# MCU.net
KiCad netlist of a schematic drawn in Altium Designer
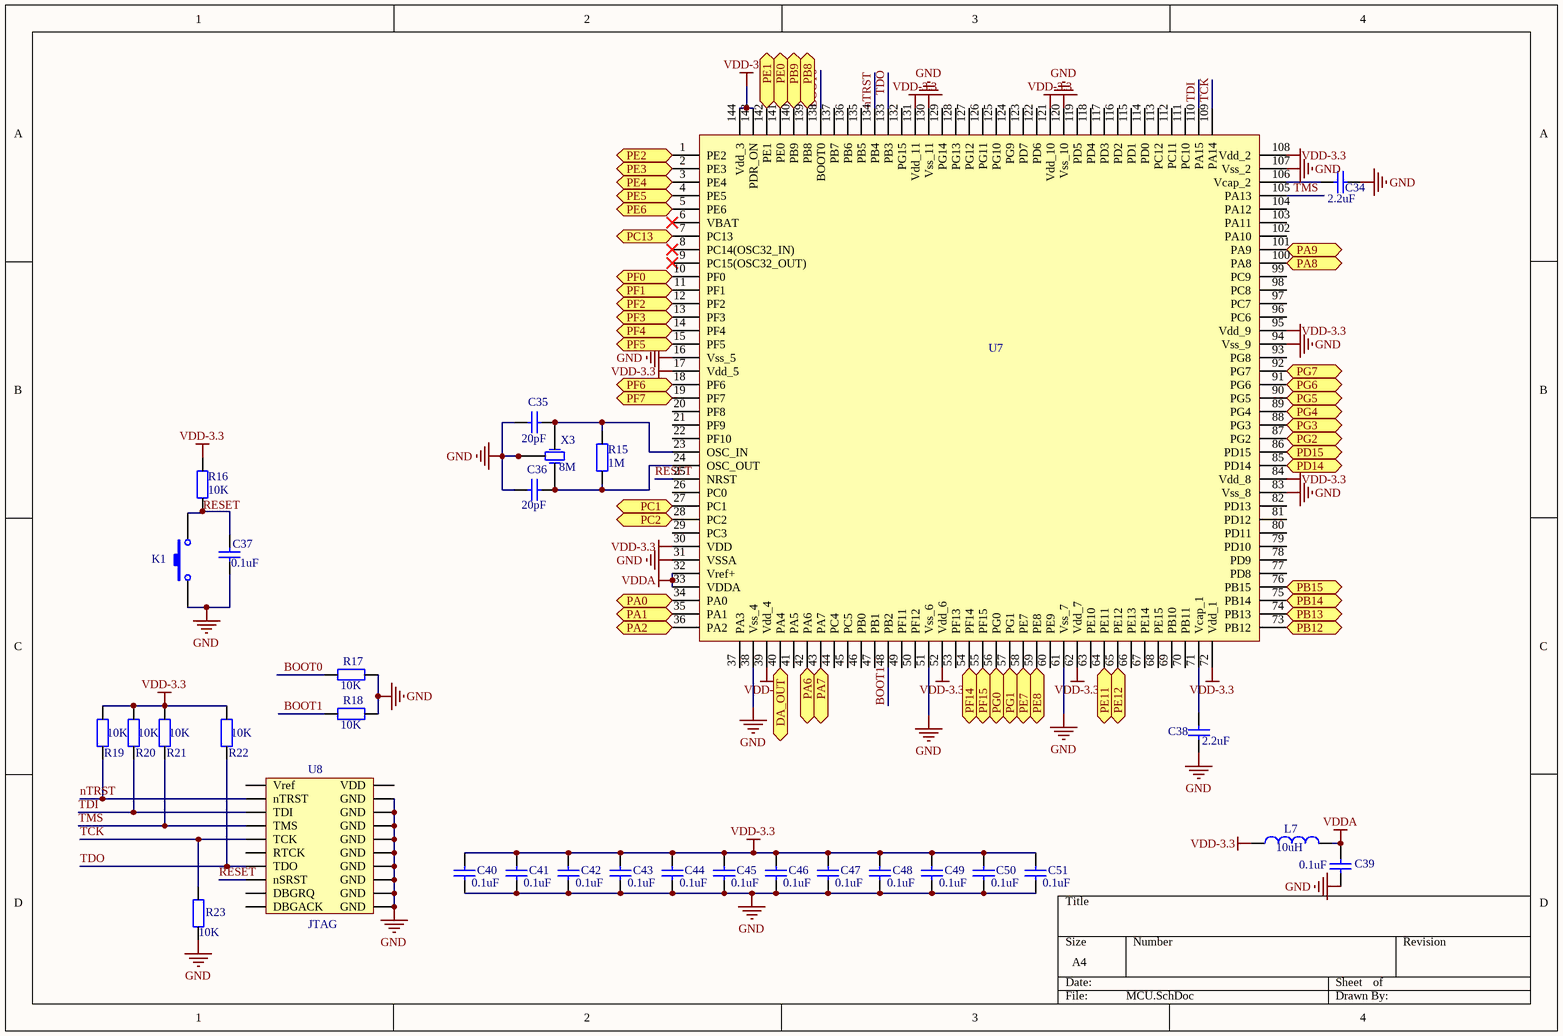
[diagram p0: MCU.SchDoc]

(export (version "E")
  (design (tool "Eeschema 10.0.6"))
  (components
    (comp (ref "C34")
      (value "2.2uF")
      (footprint "0603")
      (fields (field (name "Comment") "Capacitor-0603"))
      (libsource (lib "原理图库") (part "Capacitor-0603"))
    )
    (comp (ref "C35")
      (value "20pF")
      (footprint "0603")
      (fields (field (name "Comment") "Capacitor-0603"))
      (libsource (lib "原理图库") (part "Capacitor-0603"))
    )
    (comp (ref "C36")
      (value "20pF")
      (footprint "0603")
      (fields (field (name "Comment") "Capacitor-0603"))
      (libsource (lib "原理图库") (part "Capacitor-0603"))
    )
    (comp (ref "C37")
      (value "0.1uF")
      (footprint "0603")
      (fields (field (name "Comment") "Capacitor-0805"))
      (libsource (lib "原理图库") (part "Capacitor-0805"))
    )
    (comp (ref "C38")
      (value "2.2uF")
      (footprint "0603")
      (fields (field (name "Comment") "Capacitor-0603"))
      (libsource (lib "原理图库") (part "Capacitor-0603"))
    )
    (comp (ref "C39")
      (value "0.1uF")
      (footprint "0603")
      (fields (field (name "Comment") "Capacitor-0805"))
      (libsource (lib "集成库—大岐") (part "Capacitor-0805"))
    )
    (comp (ref "C40")
      (value "0.1uF")
      (footprint "0603")
      (fields (field (name "Comment") "Capacitor-0603"))
      (libsource (lib "原理图库") (part "Capacitor-0603"))
    )
    (comp (ref "C41")
      (value "0.1uF")
      (footprint "0603")
      (fields (field (name "Comment") "Capacitor-0603"))
      (libsource (lib "原理图库") (part "Capacitor-0603"))
    )
    (comp (ref "C42")
      (value "0.1uF")
      (footprint "0603")
      (fields (field (name "Comment") "Capacitor-0603"))
      (libsource (lib "原理图库") (part "Capacitor-0603"))
    )
    (comp (ref "C43")
      (value "0.1uF")
      (footprint "0603")
      (fields (field (name "Comment") "Capacitor-0603"))
      (libsource (lib "原理图库") (part "Capacitor-0603"))
    )
    (comp (ref "C44")
      (value "0.1uF")
      (footprint "0603")
      (fields (field (name "Comment") "Capacitor-0603"))
      (libsource (lib "原理图库") (part "Capacitor-0603"))
    )
    (comp (ref "C45")
      (value "0.1uF")
      (footprint "0603")
      (fields (field (name "Comment") "Capacitor-0603"))
      (libsource (lib "原理图库") (part "Capacitor-0603"))
    )
    (comp (ref "C46")
      (value "0.1uF")
      (footprint "0603")
      (fields (field (name "Comment") "Capacitor-0603"))
      (libsource (lib "原理图库") (part "Capacitor-0603"))
    )
    (comp (ref "C47")
      (value "0.1uF")
      (footprint "0603")
      (fields (field (name "Comment") "Capacitor-0603"))
      (libsource (lib "原理图库") (part "Capacitor-0603"))
    )
    (comp (ref "C48")
      (value "0.1uF")
      (footprint "0603")
      (fields (field (name "Comment") "Capacitor-0603"))
      (libsource (lib "原理图库") (part "Capacitor-0603"))
    )
    (comp (ref "C49")
      (value "0.1uF")
      (footprint "0603")
      (fields (field (name "Comment") "Capacitor-0603"))
      (libsource (lib "原理图库") (part "Capacitor-0603"))
    )
    (comp (ref "C50")
      (value "0.1uF")
      (footprint "0603")
      (fields (field (name "Comment") "Capacitor-0603"))
      (libsource (lib "原理图库") (part "Capacitor-0603"))
    )
    (comp (ref "C51")
      (value "0.1uF")
      (footprint "0603")
      (fields (field (name "Comment") "Capacitor-0603"))
      (libsource (lib "原理图库") (part "Capacitor-0603"))
    )
    (comp (ref "K1") (value "按键") (footprint "贴片按键") (libsource (lib "原理图库") (part "按键")))
    (comp (ref "L7")
      (value "10uH")
      (footprint "0805")
      (fields (field (name "Comment") "Inductor"))
      (libsource (lib "集成库—大岐") (part "Inductor"))
    )
    (comp (ref "R15")
      (value "1M")
      (footprint "0603")
      (fields (field (name "Comment") "Resistor-0603"))
      (libsource (lib "原理图库") (part "Resistor-0603"))
    )
    (comp (ref "R16")
      (value "10K")
      (footprint "0603")
      (fields (field (name "Comment") "Resistor-0805"))
      (libsource (lib "原理图库") (part "Resistor-0805"))
    )
    (comp (ref "R17")
      (value "10K")
      (footprint "0603")
      (fields (field (name "Comment") "Resistor-0805"))
      (libsource (lib "") (part "Resistor-0805_1"))
    )
    (comp (ref "R18")
      (value "10K")
      (footprint "0603")
      (fields (field (name "Comment") "Resistor-0805"))
      (libsource (lib "") (part "Resistor-0805_1"))
    )
    (comp (ref "R19")
      (value "10K")
      (footprint "0603")
      (fields (field (name "Comment") "Resistor-0805"))
      (libsource (lib "原理图库") (part "Resistor-0805"))
    )
    (comp (ref "R20")
      (value "10K")
      (footprint "0603")
      (fields (field (name "Comment") "Resistor-0805"))
      (libsource (lib "原理图库") (part "Resistor-0805"))
    )
    (comp (ref "R21")
      (value "10K")
      (footprint "0603")
      (fields (field (name "Comment") "Resistor-0805"))
      (libsource (lib "原理图库") (part "Resistor-0805"))
    )
    (comp (ref "R22")
      (value "10K")
      (footprint "0603")
      (fields (field (name "Comment") "Resistor-0805"))
      (libsource (lib "原理图库") (part "Resistor-0805"))
    )
    (comp (ref "R23")
      (value "10K")
      (footprint "0603")
      (fields (field (name "Comment") "Resistor-0805"))
      (libsource (lib "原理图库") (part "Resistor-0805"))
    )
    (comp (ref "U7")
      (value "STM32F407ZET6")
      (footprint "Stm32f407ZET6 - duplicate")
      (fields (field (name "Comment") "STM32F407ZGT6"))
      (libsource (lib "原理图库") (part "STM32F407ZET6"))
    )
    (comp (ref "U8") (value "JTAG") (footprint "JTAG-20") (libsource (lib "原理图库") (part "JTAG")))
    (comp (ref "X3")
      (value "8M")
      (footprint "3225无源晶振")
      (fields (field (name "Comment") "3225无源晶振"))
      (libsource (lib "原理图库") (part "3225无源晶振"))
    )
  )
  (nets
    (net (code "1") (name "/BOOT0") (class "Default")
      (node (ref "R17") (pin "2") (pinfunction "2_2") (pintype "passive"))
      (node (ref "U7") (pin "138") (pinfunction "BOOT0_138") (pintype "passive"))
    )
    (net (code "2") (name "/BOOT1") (class "Default")
      (node (ref "R18") (pin "2") (pinfunction "2_2") (pintype "passive"))
      (node (ref "U7") (pin "48") (pinfunction "PB2_48") (pintype "passive"))
    )
    (net (code "3") (name "/DA_OUT") (class "Default")
      (node (ref "U7") (pin "40") (pinfunction "PA4_40") (pintype "passive"))
    )
    (net (code "4") (name "/PA0") (class "Default")
      (node (ref "U7") (pin "34") (pinfunction "PA0_34") (pintype "passive"))
    )
    (net (code "5") (name "/PA1") (class "Default")
      (node (ref "U7") (pin "35") (pinfunction "PA1_35") (pintype "passive"))
    )
    (net (code "6") (name "/PA2") (class "Default")
      (node (ref "U7") (pin "36") (pinfunction "PA2_36") (pintype "passive"))
    )
    (net (code "7") (name "/PA6") (class "Default")
      (node (ref "U7") (pin "42") (pinfunction "PA6_42") (pintype "passive"))
    )
    (net (code "8") (name "/PA7") (class "Default")
      (node (ref "U7") (pin "43") (pinfunction "PA7_43") (pintype "passive"))
    )
    (net (code "9") (name "/PA8") (class "Default")
      (node (ref "U7") (pin "100") (pinfunction "PA8_100") (pintype "passive"))
    )
    (net (code "10") (name "/PA9") (class "Default")
      (node (ref "U7") (pin "101") (pinfunction "PA9_101") (pintype "passive"))
    )
    (net (code "11") (name "/PB8") (class "Default")
      (node (ref "U7") (pin "139") (pinfunction "PB8_139") (pintype "passive"))
    )
    (net (code "12") (name "/PB9") (class "Default")
      (node (ref "U7") (pin "140") (pinfunction "PB9_140") (pintype "passive"))
    )
    (net (code "13") (name "/PB12") (class "Default")
      (node (ref "U7") (pin "73") (pinfunction "PB12_73") (pintype "passive"))
    )
    (net (code "14") (name "/PB13") (class "Default")
      (node (ref "U7") (pin "74") (pinfunction "PB13_74") (pintype "passive"))
    )
    (net (code "15") (name "/PB14") (class "Default")
      (node (ref "U7") (pin "75") (pinfunction "PB14_75") (pintype "passive"))
    )
    (net (code "16") (name "/PB15") (class "Default")
      (node (ref "U7") (pin "76") (pinfunction "PB15_76") (pintype "passive"))
    )
    (net (code "17") (name "/PC1") (class "Default")
      (node (ref "U7") (pin "27") (pinfunction "PC1_27") (pintype "passive"))
    )
    (net (code "18") (name "/PC2") (class "Default")
      (node (ref "U7") (pin "28") (pinfunction "PC2_28") (pintype "passive"))
    )
    (net (code "19") (name "/PC13") (class "Default")
      (node (ref "U7") (pin "7") (pinfunction "PC13_7") (pintype "passive"))
    )
    (net (code "20") (name "/PD14") (class "Default")
      (node (ref "U7") (pin "85") (pinfunction "PD14_85") (pintype "passive"))
    )
    (net (code "21") (name "/PD15") (class "Default")
      (node (ref "U7") (pin "86") (pinfunction "PD15_86") (pintype "passive"))
    )
    (net (code "22") (name "/PE0") (class "Default")
      (node (ref "U7") (pin "141") (pinfunction "PE0_141") (pintype "passive"))
    )
    (net (code "23") (name "/PE1") (class "Default")
      (node (ref "U7") (pin "142") (pinfunction "PE1_142") (pintype "passive"))
    )
    (net (code "24") (name "/PE2") (class "Default")
      (node (ref "U7") (pin "1") (pinfunction "PE2_1") (pintype "passive"))
    )
    (net (code "25") (name "/PE3") (class "Default")
      (node (ref "U7") (pin "2") (pinfunction "PE3_2") (pintype "passive"))
    )
    (net (code "26") (name "/PE4") (class "Default")
      (node (ref "U7") (pin "3") (pinfunction "PE4_3") (pintype "passive"))
    )
    (net (code "27") (name "/PE5") (class "Default")
      (node (ref "U7") (pin "4") (pinfunction "PE5_4") (pintype "passive"))
    )
    (net (code "28") (name "/PE6") (class "Default")
      (node (ref "U7") (pin "5") (pinfunction "PE6_5") (pintype "passive"))
    )
    (net (code "29") (name "/PE7") (class "Default")
      (node (ref "U7") (pin "58") (pinfunction "PE7_58") (pintype "passive"))
    )
    (net (code "30") (name "/PE8") (class "Default")
      (node (ref "U7") (pin "59") (pinfunction "PE8_59") (pintype "passive"))
    )
    (net (code "31") (name "/PE11") (class "Default")
      (node (ref "U7") (pin "64") (pinfunction "PE11_64") (pintype "passive"))
    )
    (net (code "32") (name "/PE12") (class "Default")
      (node (ref "U7") (pin "65") (pinfunction "PE12_65") (pintype "passive"))
    )
    (net (code "33") (name "/PF0") (class "Default")
      (node (ref "U7") (pin "10") (pinfunction "PF0_10") (pintype "passive"))
    )
    (net (code "34") (name "/PF1") (class "Default")
      (node (ref "U7") (pin "11") (pinfunction "PF1_11") (pintype "passive"))
    )
    (net (code "35") (name "/PF2") (class "Default")
      (node (ref "U7") (pin "12") (pinfunction "PF2_12") (pintype "passive"))
    )
    (net (code "36") (name "/PF3") (class "Default")
      (node (ref "U7") (pin "13") (pinfunction "PF3_13") (pintype "passive"))
    )
    (net (code "37") (name "/PF4") (class "Default")
      (node (ref "U7") (pin "14") (pinfunction "PF4_14") (pintype "passive"))
    )
    (net (code "38") (name "/PF5") (class "Default")
      (node (ref "U7") (pin "15") (pinfunction "PF5_15") (pintype "passive"))
    )
    (net (code "39") (name "/PF6") (class "Default")
      (node (ref "U7") (pin "18") (pinfunction "PF6_18") (pintype "passive"))
    )
    (net (code "40") (name "/PF7") (class "Default")
      (node (ref "U7") (pin "19") (pinfunction "PF7_19") (pintype "passive"))
    )
    (net (code "41") (name "/PF14") (class "Default")
      (node (ref "U7") (pin "54") (pinfunction "PF14_54") (pintype "passive"))
    )
    (net (code "42") (name "/PF15") (class "Default")
      (node (ref "U7") (pin "55") (pinfunction "PF15_55") (pintype "passive"))
    )
    (net (code "43") (name "/PG0") (class "Default")
      (node (ref "U7") (pin "56") (pinfunction "PG0_56") (pintype "passive"))
    )
    (net (code "44") (name "/PG1") (class "Default")
      (node (ref "U7") (pin "57") (pinfunction "PG1_57") (pintype "passive"))
    )
    (net (code "45") (name "/PG2") (class "Default")
      (node (ref "U7") (pin "87") (pinfunction "PG2_87") (pintype "passive"))
    )
    (net (code "46") (name "/PG3") (class "Default")
      (node (ref "U7") (pin "88") (pinfunction "PG3_88") (pintype "passive"))
    )
    (net (code "47") (name "/PG4") (class "Default")
      (node (ref "U7") (pin "89") (pinfunction "PG4_89") (pintype "passive"))
    )
    (net (code "48") (name "/PG5") (class "Default")
      (node (ref "U7") (pin "90") (pinfunction "PG5_90") (pintype "passive"))
    )
    (net (code "49") (name "/PG6") (class "Default")
      (node (ref "U7") (pin "91") (pinfunction "PG6_91") (pintype "passive"))
    )
    (net (code "50") (name "/PG7") (class "Default")
      (node (ref "U7") (pin "92") (pinfunction "PG7_92") (pintype "passive"))
    )
    (net (code "51") (name "/RESET") (class "Default")
      (node (ref "C37") (pin "2") (pinfunction "2_2") (pintype "passive"))
      (node (ref "K1") (pin "2") (pinfunction "2_2") (pintype "passive"))
      (node (ref "R16") (pin "1") (pinfunction "1_1") (pintype "passive"))
      (node (ref "U7") (pin "25") (pinfunction "NRST_25") (pintype "passive"))
      (node (ref "U8") (pin "15") (pinfunction "nSRST_15") (pintype "passive"))
    )
    (net (code "52") (name "/TCK") (class "Default")
      (node (ref "R23") (pin "2") (pinfunction "2_2") (pintype "passive"))
      (node (ref "U7") (pin "109") (pinfunction "PA14_109") (pintype "passive"))
      (node (ref "U8") (pin "9") (pinfunction "TCK_9") (pintype "passive"))
    )
    (net (code "53") (name "/TDI") (class "Default")
      (node (ref "R20") (pin "1") (pinfunction "1_1") (pintype "passive"))
      (node (ref "U7") (pin "110") (pinfunction "PA15_110") (pintype "passive"))
      (node (ref "U8") (pin "5") (pinfunction "TDI_5") (pintype "passive"))
    )
    (net (code "54") (name "/TDO") (class "Default")
      (node (ref "R22") (pin "1") (pinfunction "1_1") (pintype "passive"))
      (node (ref "U7") (pin "133") (pinfunction "PB3_133") (pintype "passive"))
      (node (ref "U8") (pin "13") (pinfunction "TDO_13") (pintype "passive"))
    )
    (net (code "55") (name "/TMS") (class "Default")
      (node (ref "R21") (pin "1") (pinfunction "1_1") (pintype "passive"))
      (node (ref "U7") (pin "105") (pinfunction "PA13_105") (pintype "passive"))
      (node (ref "U8") (pin "7") (pinfunction "TMS_7") (pintype "passive"))
    )
    (net (code "56") (name "/nTRST") (class "Default")
      (node (ref "R19") (pin "1") (pinfunction "1_1") (pintype "passive"))
      (node (ref "U7") (pin "134") (pinfunction "PB4_134") (pintype "passive"))
      (node (ref "U8") (pin "3") (pinfunction "nTRST_3") (pintype "passive"))
    )
    (net (code "57") (name "GND") (class "Default")
      (node (ref "C34") (pin "2") (pinfunction "2_2") (pintype "passive"))
      (node (ref "C35") (pin "1") (pinfunction "1_1") (pintype "passive"))
      (node (ref "C36") (pin "1") (pinfunction "1_1") (pintype "passive"))
      (node (ref "C37") (pin "1") (pinfunction "1_1") (pintype "passive"))
      (node (ref "C38") (pin "1") (pinfunction "1_1") (pintype "passive"))
      (node (ref "C39") (pin "1") (pinfunction "1_1") (pintype "passive"))
      (node (ref "C40") (pin "1") (pinfunction "1_1") (pintype "passive"))
      (node (ref "C41") (pin "1") (pinfunction "1_1") (pintype "passive"))
      (node (ref "C42") (pin "1") (pinfunction "1_1") (pintype "passive"))
      (node (ref "C43") (pin "1") (pinfunction "1_1") (pintype "passive"))
      (node (ref "C44") (pin "1") (pinfunction "1_1") (pintype "passive"))
      (node (ref "C45") (pin "1") (pinfunction "1_1") (pintype "passive"))
      (node (ref "C46") (pin "1") (pinfunction "1_1") (pintype "passive"))
      (node (ref "C47") (pin "1") (pinfunction "1_1") (pintype "passive"))
      (node (ref "C48") (pin "1") (pinfunction "1_1") (pintype "passive"))
      (node (ref "C49") (pin "1") (pinfunction "1_1") (pintype "passive"))
      (node (ref "C50") (pin "1") (pinfunction "1_1") (pintype "passive"))
      (node (ref "C51") (pin "1") (pinfunction "1_1") (pintype "passive"))
      (node (ref "K1") (pin "1") (pinfunction "1_1") (pintype "passive"))
      (node (ref "R17") (pin "1") (pinfunction "1_1") (pintype "passive"))
      (node (ref "R18") (pin "1") (pinfunction "1_1") (pintype "passive"))
      (node (ref "R23") (pin "1") (pinfunction "1_1") (pintype "passive"))
      (node (ref "U7") (pin "107") (pinfunction "Vss_2_107") (pintype "passive"))
      (node (ref "U7") (pin "120") (pinfunction "Vss_10_120") (pintype "passive"))
      (node (ref "U7") (pin "130") (pinfunction "Vss_11_130") (pintype "passive"))
      (node (ref "U7") (pin "16") (pinfunction "Vss_5_16") (pintype "passive"))
      (node (ref "U7") (pin "31") (pinfunction "VSSA_31") (pintype "passive"))
      (node (ref "U7") (pin "38") (pinfunction "Vss_4_38") (pintype "passive"))
      (node (ref "U7") (pin "51") (pinfunction "Vss_6_51") (pintype "passive"))
      (node (ref "U7") (pin "61") (pinfunction "Vss_7_61") (pintype "passive"))
      (node (ref "U7") (pin "83") (pinfunction "Vss_8_83") (pintype "passive"))
      (node (ref "U7") (pin "94") (pinfunction "Vss_9_94") (pintype "passive"))
      (node (ref "U8") (pin "10") (pinfunction "GND_10") (pintype "passive"))
      (node (ref "U8") (pin "12") (pinfunction "GND_12") (pintype "passive"))
      (node (ref "U8") (pin "14") (pinfunction "GND_14") (pintype "passive"))
      (node (ref "U8") (pin "16") (pinfunction "GND_16") (pintype "passive"))
      (node (ref "U8") (pin "18") (pinfunction "GND_18") (pintype "passive"))
      (node (ref "U8") (pin "20") (pinfunction "GND_20") (pintype "passive"))
      (node (ref "U8") (pin "4") (pinfunction "GND_4") (pintype "passive"))
      (node (ref "U8") (pin "6") (pinfunction "GND_6") (pintype "passive"))
      (node (ref "U8") (pin "8") (pinfunction "GND_8") (pintype "passive"))
      (node (ref "X3") (pin "2") (pinfunction "GND_2") (pintype "passive"))
      (node (ref "X3") (pin "4") (pinfunction "GND_4") (pintype "passive"))
    )
    (net (code "58") (name "Net-(U7-OSC_IN)") (class "Default")
      (node (ref "C35") (pin "2") (pinfunction "2_2") (pintype "passive"))
      (node (ref "R15") (pin "2") (pinfunction "2_2") (pintype "passive"))
      (node (ref "U7") (pin "23") (pinfunction "OSC_IN_23") (pintype "passive"))
      (node (ref "X3") (pin "1") (pinfunction "OSC1_1") (pintype "passive"))
    )
    (net (code "59") (name "Net-(U7-OSC_OUT)") (class "Default")
      (node (ref "C36") (pin "2") (pinfunction "2_2") (pintype "passive"))
      (node (ref "R15") (pin "1") (pinfunction "1_1") (pintype "passive"))
      (node (ref "U7") (pin "24") (pinfunction "OSC_OUT_24") (pintype "passive"))
      (node (ref "X3") (pin "3") (pinfunction "OSC2_3") (pintype "passive"))
    )
    (net (code "60") (name "Net-(U7-Vcap_1)") (class "Default")
      (node (ref "C38") (pin "2") (pinfunction "2_2") (pintype "passive"))
      (node (ref "U7") (pin "71") (pinfunction "Vcap_1_71") (pintype "passive"))
    )
    (net (code "61") (name "Net-(U7-Vcap_2)") (class "Default")
      (node (ref "C34") (pin "1") (pinfunction "1_1") (pintype "passive"))
      (node (ref "U7") (pin "106") (pinfunction "Vcap_2_106") (pintype "passive"))
    )
    (net (code "62") (name "VDD-3.3") (class "Default")
      (node (ref "C40") (pin "2") (pinfunction "2_2") (pintype "passive"))
      (node (ref "C41") (pin "2") (pinfunction "2_2") (pintype "passive"))
      (node (ref "C42") (pin "2") (pinfunction "2_2") (pintype "passive"))
      (node (ref "C43") (pin "2") (pinfunction "2_2") (pintype "passive"))
      (node (ref "C44") (pin "2") (pinfunction "2_2") (pintype "passive"))
      (node (ref "C45") (pin "2") (pinfunction "2_2") (pintype "passive"))
      (node (ref "C46") (pin "2") (pinfunction "2_2") (pintype "passive"))
      (node (ref "C47") (pin "2") (pinfunction "2_2") (pintype "passive"))
      (node (ref "C48") (pin "2") (pinfunction "2_2") (pintype "passive"))
      (node (ref "C49") (pin "2") (pinfunction "2_2") (pintype "passive"))
      (node (ref "C50") (pin "2") (pinfunction "2_2") (pintype "passive"))
      (node (ref "C51") (pin "2") (pinfunction "2_2") (pintype "passive"))
      (node (ref "L7") (pin "1") (pinfunction "1_1") (pintype "passive"))
      (node (ref "R16") (pin "2") (pinfunction "2_2") (pintype "passive"))
      (node (ref "R19") (pin "2") (pinfunction "2_2") (pintype "passive"))
      (node (ref "R20") (pin "2") (pinfunction "2_2") (pintype "passive"))
      (node (ref "R21") (pin "2") (pinfunction "2_2") (pintype "passive"))
      (node (ref "R22") (pin "2") (pinfunction "2_2") (pintype "passive"))
      (node (ref "U7") (pin "108") (pinfunction "Vdd_2_108") (pintype "passive"))
      (node (ref "U7") (pin "121") (pinfunction "Vdd_10_121") (pintype "passive"))
      (node (ref "U7") (pin "131") (pinfunction "Vdd_11_131") (pintype "passive"))
      (node (ref "U7") (pin "143") (pinfunction "PDR_ON_143") (pintype "passive"))
      (node (ref "U7") (pin "144") (pinfunction "Vdd_3_144") (pintype "passive"))
      (node (ref "U7") (pin "17") (pinfunction "Vdd_5_17") (pintype "passive"))
      (node (ref "U7") (pin "30") (pinfunction "VDD_30") (pintype "passive"))
      (node (ref "U7") (pin "39") (pinfunction "Vdd_4_39") (pintype "passive"))
      (node (ref "U7") (pin "52") (pinfunction "Vdd_6_52") (pintype "passive"))
      (node (ref "U7") (pin "62") (pinfunction "Vdd_7_62") (pintype "passive"))
      (node (ref "U7") (pin "72") (pinfunction "Vdd_1_72") (pintype "passive"))
      (node (ref "U7") (pin "84") (pinfunction "Vdd_8_84") (pintype "passive"))
      (node (ref "U7") (pin "95") (pinfunction "Vdd_9_95") (pintype "passive"))
    )
    (net (code "63") (name "VDDA") (class "Default")
      (node (ref "C39") (pin "2") (pinfunction "2_2") (pintype "passive"))
      (node (ref "L7") (pin "2") (pinfunction "2_2") (pintype "passive"))
      (node (ref "U7") (pin "32") (pinfunction "Vref+_32") (pintype "passive"))
      (node (ref "U7") (pin "33") (pinfunction "VDDA_33") (pintype "passive"))
    )
    (net (code "64") (name "unconnected-(U7-PA3-Pad37)") (class "Default")
      (node (ref "U7") (pin "37") (pinfunction "PA3_37") (pintype "passive"))
    )
    (net (code "65") (name "unconnected-(U7-PA5-Pad41)") (class "Default")
      (node (ref "U7") (pin "41") (pinfunction "PA5_41") (pintype "passive"))
    )
    (net (code "66") (name "unconnected-(U7-PA10-Pad102)") (class "Default")
      (node (ref "U7") (pin "102") (pinfunction "PA10_102") (pintype "passive"))
    )
    (net (code "67") (name "unconnected-(U7-PA11-Pad103)") (class "Default")
      (node (ref "U7") (pin "103") (pinfunction "PA11_103") (pintype "passive"))
    )
    (net (code "68") (name "unconnected-(U7-PA12-Pad104)") (class "Default")
      (node (ref "U7") (pin "104") (pinfunction "PA12_104") (pintype "passive"))
    )
    (net (code "69") (name "unconnected-(U7-PB0-Pad46)") (class "Default")
      (node (ref "U7") (pin "46") (pinfunction "PB0_46") (pintype "passive"))
    )
    (net (code "70") (name "unconnected-(U7-PB1-Pad47)") (class "Default")
      (node (ref "U7") (pin "47") (pinfunction "PB1_47") (pintype "passive"))
    )
    (net (code "71") (name "unconnected-(U7-PB5-Pad135)") (class "Default")
      (node (ref "U7") (pin "135") (pinfunction "PB5_135") (pintype "passive"))
    )
    (net (code "72") (name "unconnected-(U7-PB6-Pad136)") (class "Default")
      (node (ref "U7") (pin "136") (pinfunction "PB6_136") (pintype "passive"))
    )
    (net (code "73") (name "unconnected-(U7-PB7-Pad137)") (class "Default")
      (node (ref "U7") (pin "137") (pinfunction "PB7_137") (pintype "passive"))
    )
    (net (code "74") (name "unconnected-(U7-PB10-Pad69)") (class "Default")
      (node (ref "U7") (pin "69") (pinfunction "PB10_69") (pintype "passive"))
    )
    (net (code "75") (name "unconnected-(U7-PB11-Pad70)") (class "Default")
      (node (ref "U7") (pin "70") (pinfunction "PB11_70") (pintype "passive"))
    )
    (net (code "76") (name "unconnected-(U7-PC0-Pad26)") (class "Default")
      (node (ref "U7") (pin "26") (pinfunction "PC0_26") (pintype "passive"))
    )
    (net (code "77") (name "unconnected-(U7-PC3-Pad29)") (class "Default")
      (node (ref "U7") (pin "29") (pinfunction "PC3_29") (pintype "passive"))
    )
    (net (code "78") (name "unconnected-(U7-PC4-Pad44)") (class "Default")
      (node (ref "U7") (pin "44") (pinfunction "PC4_44") (pintype "passive"))
    )
    (net (code "79") (name "unconnected-(U7-PC5-Pad45)") (class "Default")
      (node (ref "U7") (pin "45") (pinfunction "PC5_45") (pintype "passive"))
    )
    (net (code "80") (name "unconnected-(U7-PC6-Pad96)") (class "Default")
      (node (ref "U7") (pin "96") (pinfunction "PC6_96") (pintype "passive"))
    )
    (net (code "81") (name "unconnected-(U7-PC7-Pad97)") (class "Default")
      (node (ref "U7") (pin "97") (pinfunction "PC7_97") (pintype "passive"))
    )
    (net (code "82") (name "unconnected-(U7-PC8-Pad98)") (class "Default")
      (node (ref "U7") (pin "98") (pinfunction "PC8_98") (pintype "passive"))
    )
    (net (code "83") (name "unconnected-(U7-PC9-Pad99)") (class "Default")
      (node (ref "U7") (pin "99") (pinfunction "PC9_99") (pintype "passive"))
    )
    (net (code "84") (name "unconnected-(U7-PC10-Pad111)") (class "Default")
      (node (ref "U7") (pin "111") (pinfunction "PC10_111") (pintype "passive"))
    )
    (net (code "85") (name "unconnected-(U7-PC11-Pad112)") (class "Default")
      (node (ref "U7") (pin "112") (pinfunction "PC11_112") (pintype "passive"))
    )
    (net (code "86") (name "unconnected-(U7-PC12-Pad113)") (class "Default")
      (node (ref "U7") (pin "113") (pinfunction "PC12_113") (pintype "passive"))
    )
    (net (code "87") (name "unconnected-(U7-PC14(OSC32_IN)-Pad8)") (class "Default")
      (node (ref "U7") (pin "8") (pinfunction "PC14(OSC32_IN)_8") (pintype "passive+no_connect"))
    )
    (net (code "88") (name "unconnected-(U7-PC15(OSC32_OUT)-Pad9)") (class "Default")
      (node (ref "U7") (pin "9") (pinfunction "PC15(OSC32_OUT)_9") (pintype "passive+no_connect"))
    )
    (net (code "89") (name "unconnected-(U7-PD0-Pad114)") (class "Default")
      (node (ref "U7") (pin "114") (pinfunction "PD0_114") (pintype "passive"))
    )
    (net (code "90") (name "unconnected-(U7-PD1-Pad115)") (class "Default")
      (node (ref "U7") (pin "115") (pinfunction "PD1_115") (pintype "passive"))
    )
    (net (code "91") (name "unconnected-(U7-PD2-Pad116)") (class "Default")
      (node (ref "U7") (pin "116") (pinfunction "PD2_116") (pintype "passive"))
    )
    (net (code "92") (name "unconnected-(U7-PD3-Pad117)") (class "Default")
      (node (ref "U7") (pin "117") (pinfunction "PD3_117") (pintype "passive"))
    )
    (net (code "93") (name "unconnected-(U7-PD4-Pad118)") (class "Default")
      (node (ref "U7") (pin "118") (pinfunction "PD4_118") (pintype "passive"))
    )
    (net (code "94") (name "unconnected-(U7-PD5-Pad119)") (class "Default")
      (node (ref "U7") (pin "119") (pinfunction "PD5_119") (pintype "passive"))
    )
    (net (code "95") (name "unconnected-(U7-PD6-Pad122)") (class "Default")
      (node (ref "U7") (pin "122") (pinfunction "PD6_122") (pintype "passive"))
    )
    (net (code "96") (name "unconnected-(U7-PD7-Pad123)") (class "Default")
      (node (ref "U7") (pin "123") (pinfunction "PD7_123") (pintype "passive"))
    )
    (net (code "97") (name "unconnected-(U7-PD8-Pad77)") (class "Default")
      (node (ref "U7") (pin "77") (pinfunction "PD8_77") (pintype "passive"))
    )
    (net (code "98") (name "unconnected-(U7-PD9-Pad78)") (class "Default")
      (node (ref "U7") (pin "78") (pinfunction "PD9_78") (pintype "passive"))
    )
    (net (code "99") (name "unconnected-(U7-PD10-Pad79)") (class "Default")
      (node (ref "U7") (pin "79") (pinfunction "PD10_79") (pintype "passive"))
    )
    (net (code "100") (name "unconnected-(U7-PD11-Pad80)") (class "Default")
      (node (ref "U7") (pin "80") (pinfunction "PD11_80") (pintype "passive"))
    )
    (net (code "101") (name "unconnected-(U7-PD12-Pad81)") (class "Default")
      (node (ref "U7") (pin "81") (pinfunction "PD12_81") (pintype "passive"))
    )
    (net (code "102") (name "unconnected-(U7-PD13-Pad82)") (class "Default")
      (node (ref "U7") (pin "82") (pinfunction "PD13_82") (pintype "passive"))
    )
    (net (code "103") (name "unconnected-(U7-PE9-Pad60)") (class "Default")
      (node (ref "U7") (pin "60") (pinfunction "PE9_60") (pintype "passive"))
    )
    (net (code "104") (name "unconnected-(U7-PE10-Pad63)") (class "Default")
      (node (ref "U7") (pin "63") (pinfunction "PE10_63") (pintype "passive"))
    )
    (net (code "105") (name "unconnected-(U7-PE13-Pad66)") (class "Default")
      (node (ref "U7") (pin "66") (pinfunction "PE13_66") (pintype "passive"))
    )
    (net (code "106") (name "unconnected-(U7-PE14-Pad67)") (class "Default")
      (node (ref "U7") (pin "67") (pinfunction "PE14_67") (pintype "passive"))
    )
    (net (code "107") (name "unconnected-(U7-PE15-Pad68)") (class "Default")
      (node (ref "U7") (pin "68") (pinfunction "PE15_68") (pintype "passive"))
    )
    (net (code "108") (name "unconnected-(U7-PF8-Pad20)") (class "Default")
      (node (ref "U7") (pin "20") (pinfunction "PF8_20") (pintype "passive"))
    )
    (net (code "109") (name "unconnected-(U7-PF9-Pad21)") (class "Default")
      (node (ref "U7") (pin "21") (pinfunction "PF9_21") (pintype "passive"))
    )
    (net (code "110") (name "unconnected-(U7-PF10-Pad22)") (class "Default")
      (node (ref "U7") (pin "22") (pinfunction "PF10_22") (pintype "passive"))
    )
    (net (code "111") (name "unconnected-(U7-PF11-Pad49)") (class "Default")
      (node (ref "U7") (pin "49") (pinfunction "PF11_49") (pintype "passive"))
    )
    (net (code "112") (name "unconnected-(U7-PF12-Pad50)") (class "Default")
      (node (ref "U7") (pin "50") (pinfunction "PF12_50") (pintype "passive"))
    )
    (net (code "113") (name "unconnected-(U7-PF13-Pad53)") (class "Default")
      (node (ref "U7") (pin "53") (pinfunction "PF13_53") (pintype "passive"))
    )
    (net (code "114") (name "unconnected-(U7-PG8-Pad93)") (class "Default")
      (node (ref "U7") (pin "93") (pinfunction "PG8_93") (pintype "passive"))
    )
    (net (code "115") (name "unconnected-(U7-PG9-Pad124)") (class "Default")
      (node (ref "U7") (pin "124") (pinfunction "PG9_124") (pintype "passive"))
    )
    (net (code "116") (name "unconnected-(U7-PG10-Pad125)") (class "Default")
      (node (ref "U7") (pin "125") (pinfunction "PG10_125") (pintype "passive"))
    )
    (net (code "117") (name "unconnected-(U7-PG11-Pad126)") (class "Default")
      (node (ref "U7") (pin "126") (pinfunction "PG11_126") (pintype "passive"))
    )
    (net (code "118") (name "unconnected-(U7-PG12-Pad127)") (class "Default")
      (node (ref "U7") (pin "127") (pinfunction "PG12_127") (pintype "passive"))
    )
    (net (code "119") (name "unconnected-(U7-PG13-Pad128)") (class "Default")
      (node (ref "U7") (pin "128") (pinfunction "PG13_128") (pintype "passive"))
    )
    (net (code "120") (name "unconnected-(U7-PG14-Pad129)") (class "Default")
      (node (ref "U7") (pin "129") (pinfunction "PG14_129") (pintype "passive"))
    )
    (net (code "121") (name "unconnected-(U7-PG15-Pad132)") (class "Default")
      (node (ref "U7") (pin "132") (pinfunction "PG15_132") (pintype "passive"))
    )
    (net (code "122") (name "unconnected-(U7-VBAT-Pad6)") (class "Default")
      (node (ref "U7") (pin "6") (pinfunction "VBAT_6") (pintype "passive+no_connect"))
    )
    (net (code "123") (name "unconnected-(U8-DBGACK-Pad19)") (class "Default")
      (node (ref "U8") (pin "19") (pinfunction "DBGACK_19") (pintype "passive"))
    )
    (net (code "124") (name "unconnected-(U8-DBGRQ-Pad17)") (class "Default")
      (node (ref "U8") (pin "17") (pinfunction "DBGRQ_17") (pintype "passive"))
    )
    (net (code "125") (name "unconnected-(U8-RTCK-Pad11)") (class "Default")
      (node (ref "U8") (pin "11") (pinfunction "RTCK_11") (pintype "passive"))
    )
    (net (code "126") (name "unconnected-(U8-VDD-Pad2)") (class "Default")
      (node (ref "U8") (pin "2") (pinfunction "VDD_2") (pintype "passive"))
    )
    (net (code "127") (name "unconnected-(U8-Vref-Pad1)") (class "Default")
      (node (ref "U8") (pin "1") (pinfunction "Vref_1") (pintype "passive"))
    )
  )
)
